# depco_ultra.net
KiCad netlist of a schematic drawn in EAGLE
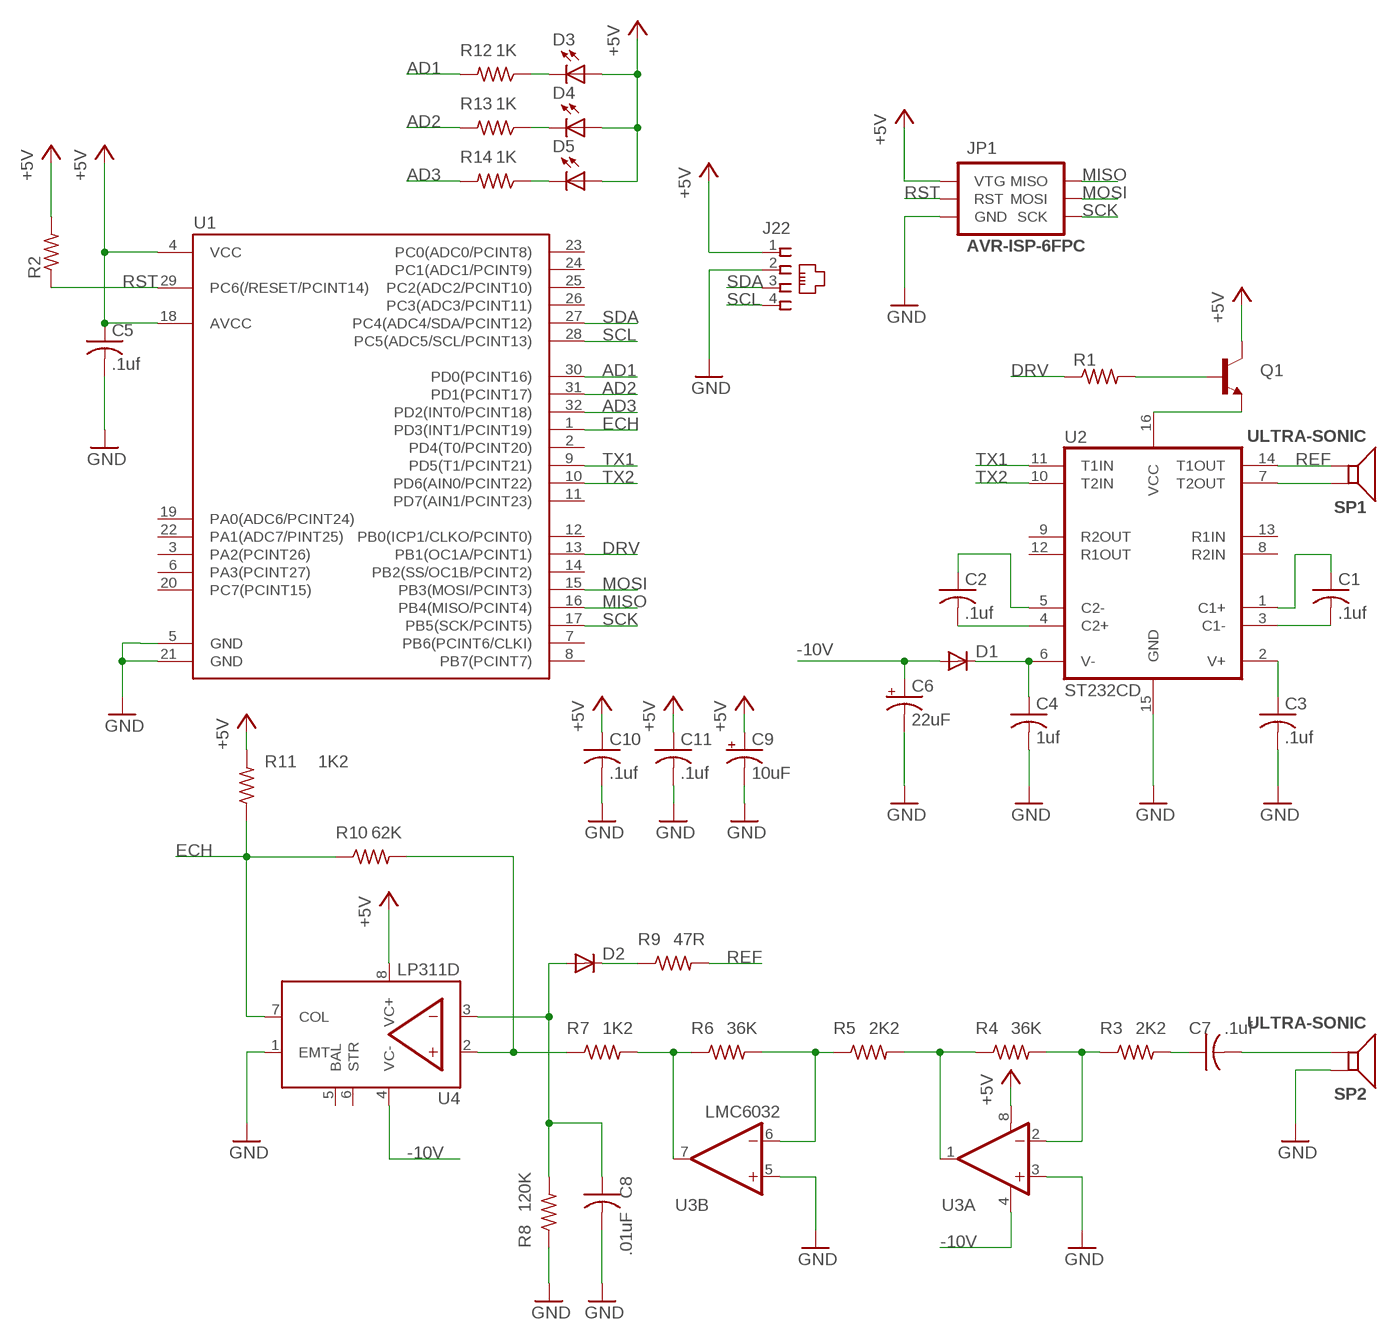
[diagram p0: schematic, sheet 1]

(export (version "E")
  (design (tool "Eeschema 10.0.6"))
  (components
    (comp (ref "C1")
      (value ".1uf")
      (footprint "eagle-import:C0805")
      (libsource (lib "eagle-import") (part "C-USC0805"))
    )
    (comp (ref "C2")
      (value ".1uf")
      (footprint "eagle-import:C0805")
      (libsource (lib "eagle-import") (part "C-USC0805"))
    )
    (comp (ref "C3")
      (value ".1uf")
      (footprint "eagle-import:C0805")
      (libsource (lib "eagle-import") (part "C-USC0805"))
    )
    (comp (ref "C4")
      (value "1uf")
      (footprint "eagle-import:C0805")
      (libsource (lib "eagle-import") (part "C-USC0805"))
    )
    (comp (ref "C5")
      (value ".1uf")
      (footprint "eagle-import:C0805")
      (libsource (lib "eagle-import") (part "C-USC0805"))
    )
    (comp (ref "C6")
      (value "22uF")
      (footprint "eagle-import:PANASONIC_D")
      (libsource (lib "eagle-import") (part "CPOL-USD"))
    )
    (comp (ref "C7")
      (value ".1uf")
      (footprint "eagle-import:C0805")
      (libsource (lib "eagle-import") (part "C-USC0805"))
    )
    (comp (ref "C8")
      (value ".01uF")
      (footprint "eagle-import:C0805")
      (libsource (lib "eagle-import") (part "C-USC0805"))
    )
    (comp (ref "C9")
      (value "10uF")
      (footprint "eagle-import:PANASONIC_D")
      (libsource (lib "eagle-import") (part "CPOL-USD"))
    )
    (comp (ref "C10")
      (value ".1uf")
      (footprint "eagle-import:C0805")
      (libsource (lib "eagle-import") (part "C-USC0805"))
    )
    (comp (ref "C11")
      (value ".1uf")
      (footprint "eagle-import:C0805")
      (libsource (lib "eagle-import") (part "C-USC0805"))
    )
    (comp (ref "D1")
      (value "DIODESOD")
      (footprint "eagle-import:SOD-323")
      (libsource (lib "eagle-import") (part "DIODESOD"))
    )
    (comp (ref "D2")
      (value "DIODESOD")
      (footprint "eagle-import:SOD-323")
      (libsource (lib "eagle-import") (part "DIODESOD"))
    )
    (comp (ref "D3")
      (value "LED_MS")
      (footprint "eagle-import:LED-0805")
      (libsource (lib "eagle-import") (part "LED_MS"))
    )
    (comp (ref "D4")
      (value "LED_MS")
      (footprint "eagle-import:LED-0805")
      (libsource (lib "eagle-import") (part "LED_MS"))
    )
    (comp (ref "D5")
      (value "LED_MS")
      (footprint "eagle-import:LED-0805")
      (libsource (lib "eagle-import") (part "LED_MS"))
    )
    (comp (ref "J22")
      (value "555165-2")
      (footprint "eagle-import:555165-2")
      (libsource (lib "eagle-import") (part "555165-2"))
    )
    (comp (ref "JP1")
      (value "AVR-ISP-6FPC")
      (footprint "eagle-import:84981-6")
      (libsource (lib "eagle-import") (part "AVR-ISP-6FPC"))
    )
    (comp (ref "Q1")
      (value "TRANSISTOR_NPNSOT23")
      (footprint "eagle-import:SOT23")
      (libsource (lib "eagle-import") (part "TRANSISTOR_NPNSOT23"))
    )
    (comp (ref "R1")
      (value "R-US_M0805")
      (footprint "eagle-import:M0805")
      (libsource (lib "eagle-import") (part "R-US_M0805"))
    )
    (comp (ref "R2")
      (value "R-US_M0805")
      (footprint "eagle-import:M0805")
      (libsource (lib "eagle-import") (part "R-US_M0805"))
    )
    (comp (ref "R3")
      (value "2K2")
      (footprint "eagle-import:M0805")
      (libsource (lib "eagle-import") (part "R-US_M0805"))
    )
    (comp (ref "R4")
      (value "36K")
      (footprint "eagle-import:M0805")
      (libsource (lib "eagle-import") (part "R-US_M0805"))
    )
    (comp (ref "R5")
      (value "2K2")
      (footprint "eagle-import:M0805")
      (libsource (lib "eagle-import") (part "R-US_M0805"))
    )
    (comp (ref "R6")
      (value "36K")
      (footprint "eagle-import:M0805")
      (libsource (lib "eagle-import") (part "R-US_M0805"))
    )
    (comp (ref "R7")
      (value "1K2")
      (footprint "eagle-import:M0805")
      (libsource (lib "eagle-import") (part "R-US_M0805"))
    )
    (comp (ref "R8")
      (value "120K")
      (footprint "eagle-import:M0805")
      (libsource (lib "eagle-import") (part "R-US_M0805"))
    )
    (comp (ref "R9")
      (value "47R")
      (footprint "eagle-import:M0805")
      (libsource (lib "eagle-import") (part "R-US_M0805"))
    )
    (comp (ref "R10")
      (value "62K")
      (footprint "eagle-import:M0805")
      (libsource (lib "eagle-import") (part "R-US_M0805"))
    )
    (comp (ref "R11")
      (value "1K2")
      (footprint "eagle-import:M0805")
      (libsource (lib "eagle-import") (part "R-US_M0805"))
    )
    (comp (ref "R12")
      (value "1K")
      (footprint "eagle-import:M0805")
      (libsource (lib "eagle-import") (part "R-US_M0805"))
    )
    (comp (ref "R13")
      (value "1K")
      (footprint "eagle-import:M0805")
      (libsource (lib "eagle-import") (part "R-US_M0805"))
    )
    (comp (ref "R14")
      (value "1K")
      (footprint "eagle-import:M0805")
      (libsource (lib "eagle-import") (part "R-US_M0805"))
    )
    (comp (ref "SP1")
      (value "ULTRA-SONIC")
      (footprint "eagle-import:400_D64INC")
      (libsource (lib "eagle-import") (part "ULTRA-SONIC"))
    )
    (comp (ref "SP2")
      (value "ULTRA-SONIC")
      (footprint "eagle-import:400_D64INC")
      (libsource (lib "eagle-import") (part "ULTRA-SONIC"))
    )
    (comp (ref "U1")
      (value "ATTINY48-QFN")
      (footprint "eagle-import:TQFP32-08")
      (libsource (lib "eagle-import") (part "ATTINY48-QFN"))
    )
    (comp (ref "U2")
      (value "ST232CD")
      (footprint "eagle-import:SO016")
      (libsource (lib "eagle-import") (part "MAX232SOIC16"))
    )
    (comp (ref "U3")
      (value "LMC6032")
      (footprint "eagle-import:SO08")
      (libsource (lib "eagle-import") (part "OPAMP-DUALU"))
    )
    (comp (ref "U4")
      (value "LP311D")
      (footprint "eagle-import:SO08")
      (libsource (lib "eagle-import") (part "LP311D"))
    )
  )
  (nets
    (net (code "1") (name "+5V") (class "Default")
      (node (ref "C10") (pin "1") (pinfunction "1_1") (pintype "passive"))
      (node (ref "C11") (pin "1") (pinfunction "1_1") (pintype "passive"))
      (node (ref "C5") (pin "1") (pinfunction "1_1") (pintype "passive"))
      (node (ref "C9") (pin "+") (pinfunction "+_+") (pintype "passive"))
      (node (ref "D3") (pin "A") (pinfunction "A_A") (pintype "passive"))
      (node (ref "D4") (pin "A") (pinfunction "A_A") (pintype "passive"))
      (node (ref "D5") (pin "A") (pinfunction "A_A") (pintype "passive"))
      (node (ref "J22") (pin "1") (pinfunction "1_1") (pintype "passive"))
      (node (ref "JP1") (pin "5") (pinfunction "VTG_5") (pintype "passive"))
      (node (ref "Q1") (pin "3") (pinfunction "C_3") (pintype "passive"))
      (node (ref "R11") (pin "2") (pinfunction "2_2") (pintype "passive"))
      (node (ref "R2") (pin "2") (pinfunction "2_2") (pintype "passive"))
      (node (ref "U1") (pin "18") (pinfunction "AVCC_18") (pintype "passive"))
      (node (ref "U1") (pin "4") (pinfunction "VCC_4") (pintype "power_in"))
      (node (ref "U3") (pin "8") (pinfunction "V+_8") (pintype "power_in"))
      (node (ref "U4") (pin "8") (pinfunction "VC+_8") (pintype "power_in"))
    )
    (net (code "2") (name "/-10V") (class "Default")
      (node (ref "C6") (pin "+") (pinfunction "+_+") (pintype "passive"))
      (node (ref "D1") (pin "2") (pinfunction "A_2") (pintype "passive"))
      (node (ref "U3") (pin "4") (pinfunction "V-_4") (pintype "power_in"))
      (node (ref "U4") (pin "4") (pinfunction "VC-_4") (pintype "power_in"))
    )
    (net (code "3") (name "/AD1") (class "Default")
      (node (ref "R12") (pin "2") (pinfunction "2_2") (pintype "passive"))
      (node (ref "U1") (pin "30") (pinfunction "PD0(PCINT16)_30") (pintype "bidirectional"))
    )
    (net (code "4") (name "/AD2") (class "Default")
      (node (ref "R13") (pin "2") (pinfunction "2_2") (pintype "passive"))
      (node (ref "U1") (pin "31") (pinfunction "PD1(PCINT17)_31") (pintype "bidirectional"))
    )
    (net (code "5") (name "/AD3") (class "Default")
      (node (ref "R14") (pin "2") (pinfunction "2_2") (pintype "passive"))
      (node (ref "U1") (pin "32") (pinfunction "PD2(INT0/PCINT18)_32") (pintype "bidirectional"))
    )
    (net (code "6") (name "/DRV") (class "Default")
      (node (ref "R1") (pin "1") (pinfunction "1_1") (pintype "passive"))
      (node (ref "U1") (pin "13") (pinfunction "PB1(OC1A/PCINT1)_13") (pintype "bidirectional"))
    )
    (net (code "7") (name "/ECH") (class "Default")
      (node (ref "R10") (pin "1") (pinfunction "1_1") (pintype "passive"))
      (node (ref "R11") (pin "1") (pinfunction "1_1") (pintype "passive"))
      (node (ref "U1") (pin "1") (pinfunction "PD3(INT1/PCINT19)_1") (pintype "bidirectional"))
      (node (ref "U4") (pin "7") (pinfunction "COL_7") (pintype "passive"))
    )
    (net (code "8") (name "/MISO") (class "Default")
      (node (ref "JP1") (pin "2") (pinfunction "MISO_2") (pintype "passive"))
      (node (ref "U1") (pin "16") (pinfunction "PB4(MISO/PCINT4)_16") (pintype "bidirectional"))
    )
    (net (code "9") (name "/MOSI") (class "Default")
      (node (ref "JP1") (pin "3") (pinfunction "MOSI_3") (pintype "passive"))
      (node (ref "U1") (pin "15") (pinfunction "PB3(MOSI/PCINT3)_15") (pintype "bidirectional"))
    )
    (net (code "10") (name "/PA3(PCINT27)") (class "Default")
      (node (ref "U1") (pin "6") (pinfunction "PA3(PCINT27)_6") (pintype "power_in"))
    )
    (net (code "11") (name "/PC7(PCINT15)") (class "Default")
      (node (ref "U1") (pin "20") (pinfunction "PC7(PCINT15)_20") (pintype "power_in"))
    )
    (net (code "12") (name "/REF") (class "Default")
      (node (ref "R9") (pin "2") (pinfunction "2_2") (pintype "passive"))
      (node (ref "SP1") (pin "2") (pinfunction "P-_2") (pintype "bidirectional"))
      (node (ref "U2") (pin "14") (pinfunction "T1OUT_14") (pintype "output"))
    )
    (net (code "13") (name "/RST") (class "Default")
      (node (ref "JP1") (pin "4") (pinfunction "RST_4") (pintype "passive"))
      (node (ref "R2") (pin "1") (pinfunction "1_1") (pintype "passive"))
      (node (ref "U1") (pin "29") (pinfunction "PC6(/RESET/PCINT14)_29") (pintype "bidirectional"))
    )
    (net (code "14") (name "/SCK") (class "Default")
      (node (ref "JP1") (pin "1") (pinfunction "SCK_1") (pintype "passive"))
      (node (ref "U1") (pin "17") (pinfunction "PB5(SCK/PCINT5)_17") (pintype "bidirectional"))
    )
    (net (code "15") (name "/SCL") (class "Default")
      (node (ref "J22") (pin "4") (pinfunction "4_4") (pintype "passive"))
      (node (ref "U1") (pin "28") (pinfunction "PC5(ADC5/SCL/PCINT13)_28") (pintype "bidirectional"))
    )
    (net (code "16") (name "/SDA") (class "Default")
      (node (ref "J22") (pin "3") (pinfunction "3_3") (pintype "passive"))
      (node (ref "U1") (pin "27") (pinfunction "PC4(ADC4/SDA/PCINT12)_27") (pintype "bidirectional"))
    )
    (net (code "17") (name "/TX1") (class "Default")
      (node (ref "U1") (pin "9") (pinfunction "PD5(T1/PCINT21)_9") (pintype "bidirectional"))
      (node (ref "U2") (pin "11") (pinfunction "T1IN_11") (pintype "input"))
    )
    (net (code "18") (name "/TX2") (class "Default")
      (node (ref "U1") (pin "10") (pinfunction "PD6(AIN0/PCINT22)_10") (pintype "bidirectional"))
      (node (ref "U2") (pin "10") (pinfunction "T2IN_10") (pintype "input"))
    )
    (net (code "19") (name "GND") (class "Default")
      (node (ref "C10") (pin "2") (pinfunction "2_2") (pintype "passive"))
      (node (ref "C11") (pin "2") (pinfunction "2_2") (pintype "passive"))
      (node (ref "C3") (pin "2") (pinfunction "2_2") (pintype "passive"))
      (node (ref "C4") (pin "2") (pinfunction "2_2") (pintype "passive"))
      (node (ref "C5") (pin "2") (pinfunction "2_2") (pintype "passive"))
      (node (ref "C6") (pin "-") (pinfunction "-_-") (pintype "passive"))
      (node (ref "C8") (pin "2") (pinfunction "2_2") (pintype "passive"))
      (node (ref "C9") (pin "-") (pinfunction "-_-") (pintype "passive"))
      (node (ref "J22") (pin "2") (pinfunction "2_2") (pintype "passive"))
      (node (ref "JP1") (pin "6") (pinfunction "GND_6") (pintype "passive"))
      (node (ref "R8") (pin "1") (pinfunction "1_1") (pintype "passive"))
      (node (ref "SP2") (pin "1") (pinfunction "P+_1") (pintype "bidirectional"))
      (node (ref "U1") (pin "21") (pinfunction "GND_21") (pintype "power_in"))
      (node (ref "U1") (pin "5") (pinfunction "GND_5") (pintype "power_in"))
      (node (ref "U2") (pin "15") (pinfunction "GND_15") (pintype "bidirectional"))
      (node (ref "U3") (pin "3") (pinfunction "+IN_3") (pintype "input"))
      (node (ref "U3") (pin "5") (pinfunction "+IN_5") (pintype "input"))
      (node (ref "U4") (pin "1") (pinfunction "EMT_1") (pintype "output"))
    )
    (net (code "20") (name "Net-(C7-Pad1)") (class "Default")
      (node (ref "C7") (pin "1") (pinfunction "1_1") (pintype "passive"))
      (node (ref "R3") (pin "2") (pinfunction "2_2") (pintype "passive"))
    )
    (net (code "21") (name "Net-(D1-C)") (class "Default")
      (node (ref "C4") (pin "1") (pinfunction "1_1") (pintype "passive"))
      (node (ref "D1") (pin "1") (pinfunction "C_1") (pintype "passive"))
      (node (ref "U2") (pin "6") (pinfunction "V-_6") (pintype "bidirectional"))
    )
    (net (code "22") (name "Net-(D2-A)") (class "Default")
      (node (ref "C8") (pin "1") (pinfunction "1_1") (pintype "passive"))
      (node (ref "D2") (pin "2") (pinfunction "A_2") (pintype "passive"))
      (node (ref "R8") (pin "2") (pinfunction "2_2") (pintype "passive"))
      (node (ref "U4") (pin "3") (pinfunction "-IN_3") (pintype "input"))
    )
    (net (code "23") (name "Net-(D2-C)") (class "Default")
      (node (ref "D2") (pin "1") (pinfunction "C_1") (pintype "passive"))
      (node (ref "R9") (pin "1") (pinfunction "1_1") (pintype "passive"))
    )
    (net (code "24") (name "Net-(D3-PadC)") (class "Default")
      (node (ref "D3") (pin "C") (pinfunction "C_C") (pintype "passive"))
      (node (ref "R12") (pin "1") (pinfunction "1_1") (pintype "passive"))
    )
    (net (code "25") (name "Net-(D4-PadC)") (class "Default")
      (node (ref "D4") (pin "C") (pinfunction "C_C") (pintype "passive"))
      (node (ref "R13") (pin "1") (pinfunction "1_1") (pintype "passive"))
    )
    (net (code "26") (name "Net-(D5-PadC)") (class "Default")
      (node (ref "D5") (pin "C") (pinfunction "C_C") (pintype "passive"))
      (node (ref "R14") (pin "1") (pinfunction "1_1") (pintype "passive"))
    )
    (net (code "27") (name "Net-(Q1-B)") (class "Default")
      (node (ref "Q1") (pin "1") (pinfunction "B_1") (pintype "passive"))
      (node (ref "R1") (pin "2") (pinfunction "2_2") (pintype "passive"))
    )
    (net (code "28") (name "Net-(Q1-E)") (class "Default")
      (node (ref "Q1") (pin "2") (pinfunction "E_2") (pintype "passive"))
      (node (ref "U2") (pin "16") (pinfunction "VCC_16") (pintype "bidirectional"))
    )
    (net (code "29") (name "Net-(SP1-P+)") (class "Default")
      (node (ref "SP1") (pin "1") (pinfunction "P+_1") (pintype "bidirectional"))
      (node (ref "U2") (pin "7") (pinfunction "T2OUT_7") (pintype "output"))
    )
    (net (code "30") (name "Net-(SP2-P-)") (class "Default")
      (node (ref "C7") (pin "2") (pinfunction "2_2") (pintype "passive"))
      (node (ref "SP2") (pin "2") (pinfunction "P-_2") (pintype "bidirectional"))
    )
    (net (code "31") (name "Net-(U2-C1+)") (class "Default")
      (node (ref "C1") (pin "1") (pinfunction "1_1") (pintype "passive"))
      (node (ref "U2") (pin "1") (pinfunction "C1+_1") (pintype "bidirectional"))
    )
    (net (code "32") (name "Net-(U2-C1-)") (class "Default")
      (node (ref "C1") (pin "2") (pinfunction "2_2") (pintype "passive"))
      (node (ref "U2") (pin "3") (pinfunction "C1-_3") (pintype "bidirectional"))
    )
    (net (code "33") (name "Net-(U2-C2+)") (class "Default")
      (node (ref "C2") (pin "2") (pinfunction "2_2") (pintype "passive"))
      (node (ref "U2") (pin "4") (pinfunction "C2+_4") (pintype "bidirectional"))
    )
    (net (code "34") (name "Net-(U2-C2-)") (class "Default")
      (node (ref "C2") (pin "1") (pinfunction "1_1") (pintype "passive"))
      (node (ref "U2") (pin "5") (pinfunction "C2-_5") (pintype "bidirectional"))
    )
    (net (code "35") (name "Net-(U2-V+)") (class "Default")
      (node (ref "C3") (pin "1") (pinfunction "1_1") (pintype "passive"))
      (node (ref "U2") (pin "2") (pinfunction "V+_2") (pintype "bidirectional"))
    )
    (net (code "36") (name "Net-(U3A--IN)") (class "Default")
      (node (ref "R3") (pin "1") (pinfunction "1_1") (pintype "passive"))
      (node (ref "R4") (pin "2") (pinfunction "2_2") (pintype "passive"))
      (node (ref "U3") (pin "2") (pinfunction "-IN_2") (pintype "input"))
    )
    (net (code "37") (name "Net-(U3A-OUT)") (class "Default")
      (node (ref "R4") (pin "1") (pinfunction "1_1") (pintype "passive"))
      (node (ref "R5") (pin "2") (pinfunction "2_2") (pintype "passive"))
      (node (ref "U3") (pin "1") (pinfunction "OUT_1") (pintype "output"))
    )
    (net (code "38") (name "Net-(U3B--IN)") (class "Default")
      (node (ref "R5") (pin "1") (pinfunction "1_1") (pintype "passive"))
      (node (ref "R6") (pin "2") (pinfunction "2_2") (pintype "passive"))
      (node (ref "U3") (pin "6") (pinfunction "-IN_6") (pintype "input"))
    )
    (net (code "39") (name "Net-(U3B-OUT)") (class "Default")
      (node (ref "R6") (pin "1") (pinfunction "1_1") (pintype "passive"))
      (node (ref "R7") (pin "2") (pinfunction "2_2") (pintype "passive"))
      (node (ref "U3") (pin "7") (pinfunction "OUT_7") (pintype "output"))
    )
    (net (code "40") (name "Net-(U4-+IN)") (class "Default")
      (node (ref "R10") (pin "2") (pinfunction "2_2") (pintype "passive"))
      (node (ref "R7") (pin "1") (pinfunction "1_1") (pintype "passive"))
      (node (ref "U4") (pin "2") (pinfunction "+IN_2") (pintype "input"))
    )
    (net (code "41") (name "unconnected-(U1-PA0(ADC6{slash}PCINT24)-Pad19)") (class "Default")
      (node (ref "U1") (pin "19") (pinfunction "PA0(ADC6/PCINT24)_19") (pintype "passive"))
    )
    (net (code "42") (name "unconnected-(U1-PA1(ADC7{slash}PINT25)-Pad22)") (class "Default")
      (node (ref "U1") (pin "22") (pinfunction "PA1(ADC7/PINT25)_22") (pintype "passive"))
    )
    (net (code "43") (name "unconnected-(U1-PA2(PCINT26)-Pad3)") (class "Default")
      (node (ref "U1") (pin "3") (pinfunction "PA2(PCINT26)_3") (pintype "passive"))
    )
    (net (code "44") (name "unconnected-(U1-PB0(ICP1{slash}CLKO{slash}PCINT0)-Pad12)") (class "Default")
      (node (ref "U1") (pin "12") (pinfunction "PB0(ICP1/CLKO/PCINT0)_12") (pintype "bidirectional"))
    )
    (net (code "45") (name "unconnected-(U1-PB2(SS{slash}OC1B{slash}PCINT2)-Pad14)") (class "Default")
      (node (ref "U1") (pin "14") (pinfunction "PB2(SS/OC1B/PCINT2)_14") (pintype "bidirectional"))
    )
    (net (code "46") (name "unconnected-(U1-PB6(PCINT6{slash}CLKI)-Pad7)") (class "Default")
      (node (ref "U1") (pin "7") (pinfunction "PB6(PCINT6/CLKI)_7") (pintype "bidirectional"))
    )
    (net (code "47") (name "unconnected-(U1-PB7(PCINT7)-Pad8)") (class "Default")
      (node (ref "U1") (pin "8") (pinfunction "PB7(PCINT7)_8") (pintype "bidirectional"))
    )
    (net (code "48") (name "unconnected-(U1-PC0(ADC0{slash}PCINT8)-Pad23)") (class "Default")
      (node (ref "U1") (pin "23") (pinfunction "PC0(ADC0/PCINT8)_23") (pintype "bidirectional"))
    )
    (net (code "49") (name "unconnected-(U1-PC1(ADC1{slash}PCINT9)-Pad24)") (class "Default")
      (node (ref "U1") (pin "24") (pinfunction "PC1(ADC1/PCINT9)_24") (pintype "bidirectional"))
    )
    (net (code "50") (name "unconnected-(U1-PC2(ADC2{slash}PCINT10)-Pad25)") (class "Default")
      (node (ref "U1") (pin "25") (pinfunction "PC2(ADC2/PCINT10)_25") (pintype "bidirectional"))
    )
    (net (code "51") (name "unconnected-(U1-PC3(ADC3{slash}PCINT11)-Pad26)") (class "Default")
      (node (ref "U1") (pin "26") (pinfunction "PC3(ADC3/PCINT11)_26") (pintype "bidirectional"))
    )
    (net (code "52") (name "unconnected-(U1-PD4(T0{slash}PCINT20)-Pad2)") (class "Default")
      (node (ref "U1") (pin "2") (pinfunction "PD4(T0/PCINT20)_2") (pintype "bidirectional"))
    )
    (net (code "53") (name "unconnected-(U1-PD7(AIN1{slash}PCINT23)-Pad11)") (class "Default")
      (node (ref "U1") (pin "11") (pinfunction "PD7(AIN1/PCINT23)_11") (pintype "bidirectional"))
    )
    (net (code "54") (name "unconnected-(U2-R1IN-Pad13)") (class "Default")
      (node (ref "U2") (pin "13") (pinfunction "R1IN_13") (pintype "input"))
    )
    (net (code "55") (name "unconnected-(U2-R1OUT-Pad12)") (class "Default")
      (node (ref "U2") (pin "12") (pinfunction "R1OUT_12") (pintype "output"))
    )
    (net (code "56") (name "unconnected-(U2-R2IN-Pad8)") (class "Default")
      (node (ref "U2") (pin "8") (pinfunction "R2IN_8") (pintype "input"))
    )
    (net (code "57") (name "unconnected-(U2-R2OUT-Pad9)") (class "Default")
      (node (ref "U2") (pin "9") (pinfunction "R2OUT_9") (pintype "output"))
    )
    (net (code "58") (name "unconnected-(U4-BAL-Pad5)") (class "Default")
      (node (ref "U4") (pin "5") (pinfunction "BAL_5") (pintype "passive"))
    )
    (net (code "59") (name "unconnected-(U4-STR-Pad6)") (class "Default")
      (node (ref "U4") (pin "6") (pinfunction "STR_6") (pintype "passive"))
    )
  )
)
